# accessory2.net
KiCad netlist of a schematic drawn in Altium Designer
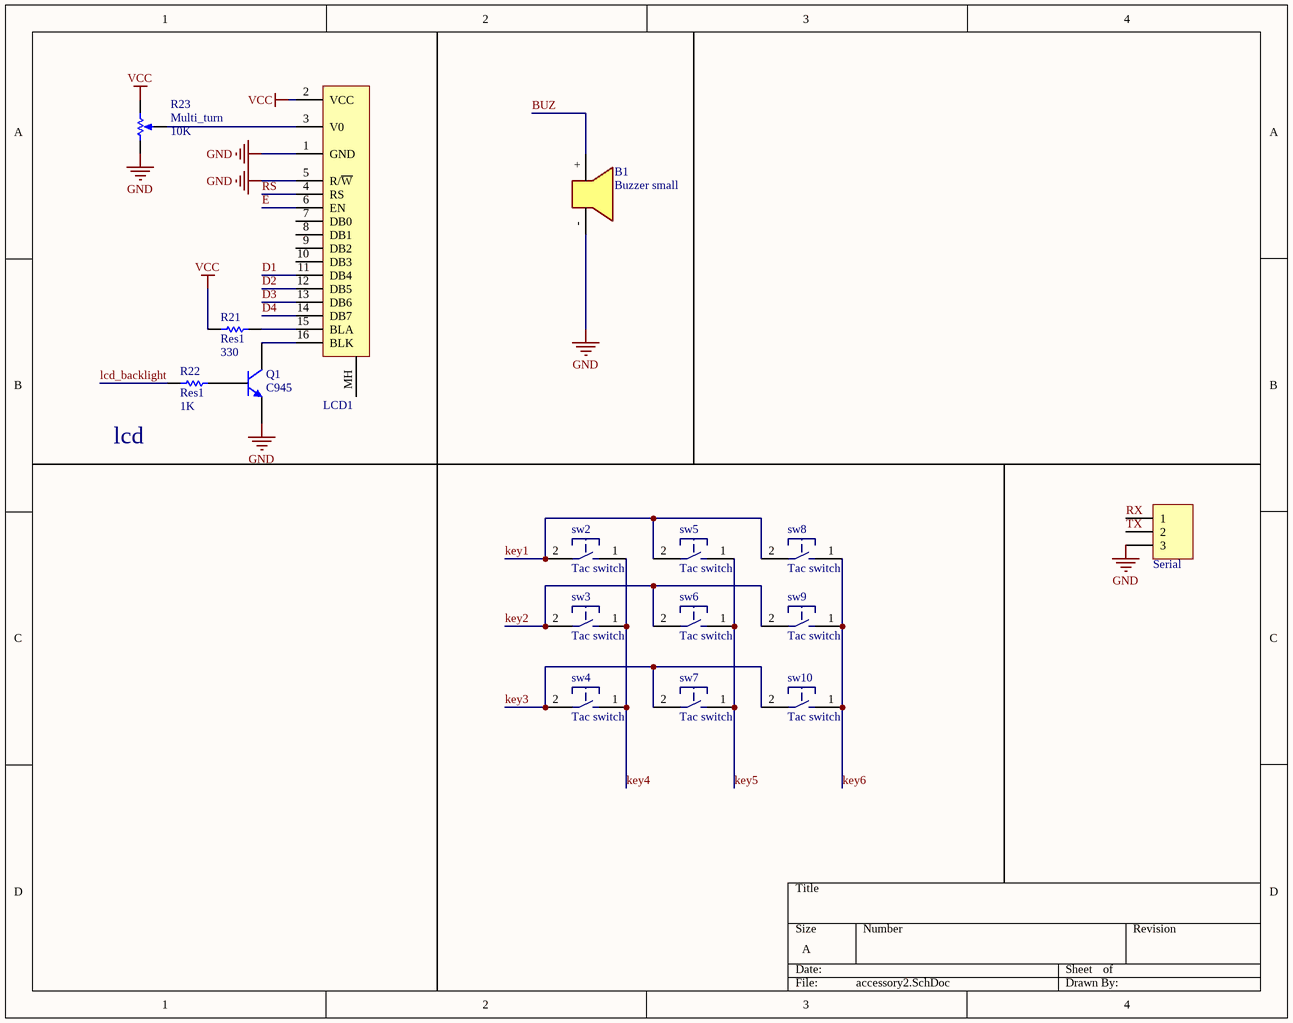
[diagram p0: accessory2.SchDoc]

(export (version "E")
  (design (tool "Eeschema 10.0.6"))
  (components
    (comp (ref "B1")
      (value "Buzzer small")
      (footprint "My_Buzzer")
      (description "5-12v small buzzer (12mm)")
      (libsource (lib "Altium library (www.AVRelec.com)") (part "Buzzer"))
    )
    (comp (ref "LCD1")
      (value "20x4")
      (footprint "LCD 16x2")
      (fields (field (name "DESIGNER") "Saeid Jorablo"))
      (libsource (lib "My Library") (part "LCD"))
    )
    (comp (ref "Q1")
      (value "C945")
      (footprint "SOT23_L")
      (description "NPN Transistor")
      (fields (field (name "DESIGNER") "Saeid Jorablo"))
      (libsource (lib "My Library") (part "C945"))
    )
    (comp (ref "R21")
      (value "Res1")
      (footprint "RES 1206/3216")
      (description "Resistor")
      (fields (field (name "ALTIUM_VALUE") "330") (field (name "PUBLISHER") "Altium Limited"))
      (libsource (lib "Miscellaneous Devices") (part "Res1"))
    )
    (comp (ref "R22")
      (value "Res1")
      (footprint "RES 1206/3216")
      (description "Resistor")
      (fields (field (name "ALTIUM_VALUE") "1K") (field (name "PUBLISHER") "Altium Limited"))
      (libsource (lib "Miscellaneous Devices") (part "Res1"))
    )
    (comp (ref "R23")
      (value "Multi_turn")
      (footprint "My_Pot_trim")
      (description "Potentiometer")
      (fields (field (name "ALTIUM_VALUE") "10K") (field (name "PUBLISHER") "Altium Limited"))
      (libsource (lib "Altium library (www.AVRelec.com)") (part "Multi_turn"))
    )
    (comp (ref "Serial") (value "H-1x3") (footprint "H-1x3") (libsource (lib "Mine-Discreet") (part "H-1x3")))
    (comp (ref "sw2")
      (value "Tac switch")
      (footprint "MY_TACTILE-PTH")
      (description "small tac switch")
      (libsource (lib "Altium library (www.AVRelec.com)") (part "Tac switch"))
    )
    (comp (ref "sw3")
      (value "Tac switch")
      (footprint "MY_TACTILE-PTH")
      (description "small tac switch")
      (libsource (lib "Altium library (www.AVRelec.com)") (part "Tac switch"))
    )
    (comp (ref "sw4")
      (value "Tac switch")
      (footprint "MY_TACTILE-PTH")
      (description "small tac switch")
      (libsource (lib "Altium library (www.AVRelec.com)") (part "Tac switch"))
    )
    (comp (ref "sw5")
      (value "Tac switch")
      (footprint "MY_TACTILE-PTH")
      (description "small tac switch")
      (libsource (lib "Altium library (www.AVRelec.com)") (part "Tac switch"))
    )
    (comp (ref "sw6")
      (value "Tac switch")
      (footprint "MY_TACTILE-PTH")
      (description "small tac switch")
      (libsource (lib "Altium library (www.AVRelec.com)") (part "Tac switch"))
    )
    (comp (ref "sw7")
      (value "Tac switch")
      (footprint "MY_TACTILE-PTH")
      (description "small tac switch")
      (libsource (lib "Altium library (www.AVRelec.com)") (part "Tac switch"))
    )
    (comp (ref "sw8")
      (value "Tac switch")
      (footprint "MY_TACTILE-PTH")
      (description "small tac switch")
      (libsource (lib "Altium library (www.AVRelec.com)") (part "Tac switch"))
    )
    (comp (ref "sw9")
      (value "Tac switch")
      (footprint "MY_TACTILE-PTH")
      (description "small tac switch")
      (libsource (lib "Altium library (www.AVRelec.com)") (part "Tac switch"))
    )
    (comp (ref "sw10")
      (value "Tac switch")
      (footprint "MY_TACTILE-PTH")
      (description "small tac switch")
      (libsource (lib "Altium library (www.AVRelec.com)") (part "Tac switch"))
    )
  )
  (nets
    (net (code "1") (name "/BUZ") (class "Default")
      (node (ref "B1") (pin "+") (pinfunction "1_+") (pintype "power_in"))
    )
    (net (code "2") (name "/D1") (class "Default")
      (node (ref "LCD1") (pin "11") (pinfunction "DB4_11") (pintype "passive"))
    )
    (net (code "3") (name "/D2") (class "Default")
      (node (ref "LCD1") (pin "12") (pinfunction "DB5_12") (pintype "passive"))
    )
    (net (code "4") (name "/D3") (class "Default")
      (node (ref "LCD1") (pin "13") (pinfunction "DB6_13") (pintype "passive"))
    )
    (net (code "5") (name "/D4") (class "Default")
      (node (ref "LCD1") (pin "14") (pinfunction "DB7_14") (pintype "passive"))
    )
    (net (code "6") (name "/E") (class "Default")
      (node (ref "LCD1") (pin "6") (pinfunction "EN_6") (pintype "passive"))
    )
    (net (code "7") (name "/RS") (class "Default")
      (node (ref "LCD1") (pin "4") (pinfunction "RS_4") (pintype "passive"))
    )
    (net (code "8") (name "/RX") (class "Default")
      (node (ref "Serial") (pin "1") (pinfunction "1_1") (pintype "passive"))
    )
    (net (code "9") (name "/TX") (class "Default")
      (node (ref "Serial") (pin "2") (pinfunction "2_2") (pintype "passive"))
    )
    (net (code "10") (name "/key1") (class "Default")
      (node (ref "sw2") (pin "2") (pinfunction "2_2") (pintype "passive"))
      (node (ref "sw5") (pin "2") (pinfunction "2_2") (pintype "passive"))
      (node (ref "sw8") (pin "2") (pinfunction "2_2") (pintype "passive"))
    )
    (net (code "11") (name "/key2") (class "Default")
      (node (ref "sw3") (pin "2") (pinfunction "2_2") (pintype "passive"))
      (node (ref "sw6") (pin "2") (pinfunction "2_2") (pintype "passive"))
      (node (ref "sw9") (pin "2") (pinfunction "2_2") (pintype "passive"))
    )
    (net (code "12") (name "/key3") (class "Default")
      (node (ref "sw10") (pin "2") (pinfunction "2_2") (pintype "passive"))
      (node (ref "sw4") (pin "2") (pinfunction "2_2") (pintype "passive"))
      (node (ref "sw7") (pin "2") (pinfunction "2_2") (pintype "passive"))
    )
    (net (code "13") (name "/key4") (class "Default")
      (node (ref "sw2") (pin "1") (pinfunction "1_1") (pintype "passive"))
      (node (ref "sw3") (pin "1") (pinfunction "1_1") (pintype "passive"))
      (node (ref "sw4") (pin "1") (pinfunction "1_1") (pintype "passive"))
    )
    (net (code "14") (name "/key5") (class "Default")
      (node (ref "sw5") (pin "1") (pinfunction "1_1") (pintype "passive"))
      (node (ref "sw6") (pin "1") (pinfunction "1_1") (pintype "passive"))
      (node (ref "sw7") (pin "1") (pinfunction "1_1") (pintype "passive"))
    )
    (net (code "15") (name "/key6") (class "Default")
      (node (ref "sw10") (pin "1") (pinfunction "1_1") (pintype "passive"))
      (node (ref "sw8") (pin "1") (pinfunction "1_1") (pintype "passive"))
      (node (ref "sw9") (pin "1") (pinfunction "1_1") (pintype "passive"))
    )
    (net (code "16") (name "/lcd_backlight") (class "Default")
      (node (ref "R22") (pin "1") (pinfunction "1_1") (pintype "passive"))
    )
    (net (code "17") (name "GND") (class "Default")
      (node (ref "B1") (pin "-") (pinfunction "2_-") (pintype "power_in"))
      (node (ref "LCD1") (pin "1") (pinfunction "GND_1") (pintype "passive"))
      (node (ref "LCD1") (pin "5") (pinfunction "R/~{W}_5") (pintype "passive"))
      (node (ref "Q1") (pin "1") (pinfunction "E_1") (pintype "passive"))
      (node (ref "R23") (pin "1") (pinfunction "TOP_1") (pintype "passive"))
      (node (ref "Serial") (pin "3") (pinfunction "3_3") (pintype "passive"))
    )
    (net (code "18") (name "Net-(LCD1-BLA)") (class "Default")
      (node (ref "LCD1") (pin "15") (pinfunction "BLA_15") (pintype "passive"))
      (node (ref "R21") (pin "2") (pinfunction "2_2") (pintype "passive"))
    )
    (net (code "19") (name "Net-(LCD1-BLK)") (class "Default")
      (node (ref "LCD1") (pin "16") (pinfunction "BLK_16") (pintype "passive"))
      (node (ref "Q1") (pin "2") (pinfunction "C_2") (pintype "passive"))
    )
    (net (code "20") (name "Net-(LCD1-V0)") (class "Default")
      (node (ref "LCD1") (pin "3") (pinfunction "V0_3") (pintype "passive"))
      (node (ref "R23") (pin "3") (pinfunction "TAP_3") (pintype "passive"))
    )
    (net (code "21") (name "Net-(Q1-B)") (class "Default")
      (node (ref "Q1") (pin "3") (pinfunction "B_3") (pintype "passive"))
      (node (ref "R22") (pin "2") (pinfunction "2_2") (pintype "passive"))
    )
    (net (code "22") (name "VCC") (class "Default")
      (node (ref "LCD1") (pin "2") (pinfunction "VCC_2") (pintype "passive"))
      (node (ref "R21") (pin "1") (pinfunction "1_1") (pintype "passive"))
      (node (ref "R23") (pin "2") (pinfunction "BOT_2") (pintype "passive"))
    )
    (net (code "23") (name "unconnected-(LCD1-DB0-Pad7)") (class "Default")
      (node (ref "LCD1") (pin "7") (pinfunction "DB0_7") (pintype "passive"))
    )
    (net (code "24") (name "unconnected-(LCD1-DB1-Pad8)") (class "Default")
      (node (ref "LCD1") (pin "8") (pinfunction "DB1_8") (pintype "passive"))
    )
    (net (code "25") (name "unconnected-(LCD1-DB2-Pad9)") (class "Default")
      (node (ref "LCD1") (pin "9") (pinfunction "DB2_9") (pintype "passive"))
    )
    (net (code "26") (name "unconnected-(LCD1-DB3-Pad10)") (class "Default")
      (node (ref "LCD1") (pin "10") (pinfunction "DB3_10") (pintype "passive"))
    )
    (net (code "27") (name "unconnected-(LCD1-PadMH)") (class "Default")
      (node (ref "LCD1") (pin "MH") (pinfunction "MH_MH") (pintype "passive"))
    )
  )
)
